# Ethernet.net
KiCad netlist of a schematic drawn in Altium Designer
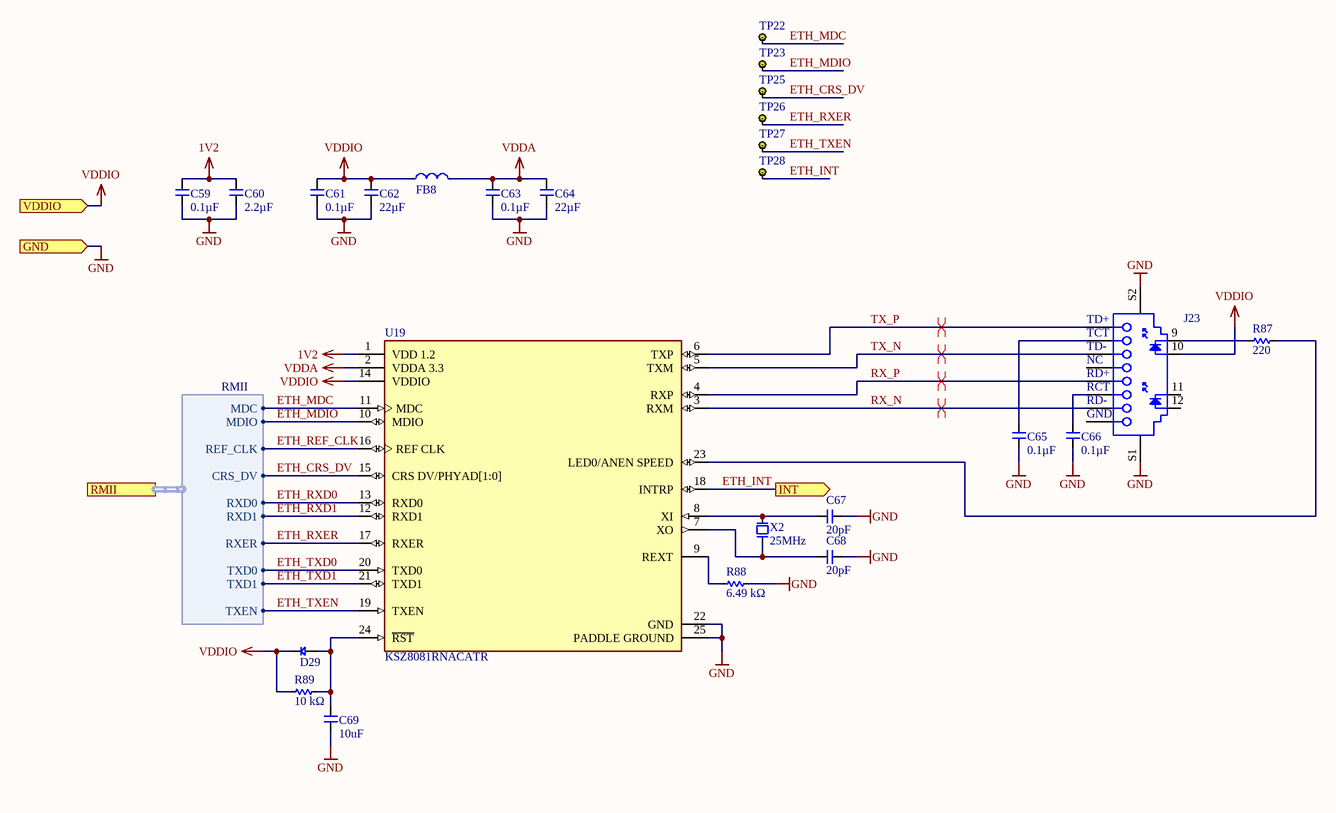
[diagram p0: Ethernet.SchDoc]

(export (version "E")
  (design (tool "Eeschema 10.0.6"))
  (components
    (comp (ref "C59")
      (value "490-1519-1-ND")
      (footprint "C0603")
      (description "CAP CER 0603 0.1µF X7R 50V 10%")
      (fields
        (field (name "MANUFACTURER") "Murata Electronics North America")
        (field (name "CAPACITANCE (SHORTHAND)") "0.1µF")
      )
      (libsource (lib "Stanford Student Space Initiative") (part "__template_cap"))
    )
    (comp (ref "C60")
      (value "490-10731-1-ND")
      (footprint "C0603")
      (description "CAP CER 2.2UF 16V X5R 0603 10%")
      (fields
        (field (name "MANUFACTURER") "Murata Electronics North America")
        (field (name "CAPACITANCE (SHORTHAND)") "2.2µF")
      )
      (libsource (lib "Stanford Student Space Initiative") (part "__template_cap"))
    )
    (comp (ref "C61")
      (value "490-1519-1-ND")
      (footprint "C0603")
      (description "CAP CER 0603 0.1µF X7R 50V 10%")
      (fields
        (field (name "MANUFACTURER") "Murata Electronics North America")
        (field (name "CAPACITANCE (SHORTHAND)") "0.1µF")
      )
      (libsource (lib "Stanford Student Space Initiative") (part "__template_cap"))
    )
    (comp (ref "C62")
      (value "1276-7076-1-ND")
      (footprint "C0603")
      (description "CAP CER 22UF 16V X5R 0603 20%")
      (fields
        (field (name "MANUFACTURER") "Samsung Electro-Mechanics")
        (field (name "CAPACITANCE (SHORTHAND)") "22µF")
      )
      (libsource (lib "Stanford Student Space Initiative") (part "__template_cap"))
    )
    (comp (ref "C63")
      (value "490-1519-1-ND")
      (footprint "C0603")
      (description "CAP CER 0603 0.1µF X7R 50V 10%")
      (fields
        (field (name "MANUFACTURER") "Murata Electronics North America")
        (field (name "CAPACITANCE (SHORTHAND)") "0.1µF")
      )
      (libsource (lib "Stanford Student Space Initiative") (part "__template_cap"))
    )
    (comp (ref "C64")
      (value "1276-7076-1-ND")
      (footprint "C0603")
      (description "CAP CER 22UF 16V X5R 0603 20%")
      (fields
        (field (name "MANUFACTURER") "Samsung Electro-Mechanics")
        (field (name "CAPACITANCE (SHORTHAND)") "22µF")
      )
      (libsource (lib "Stanford Student Space Initiative") (part "__template_cap"))
    )
    (comp (ref "C65")
      (value "490-1519-1-ND")
      (footprint "C0603")
      (description "CAP CER 0603 0.1µF X7R 50V 10%")
      (fields
        (field (name "MANUFACTURER") "Murata Electronics North America")
        (field (name "CAPACITANCE (SHORTHAND)") "0.1µF")
      )
      (libsource (lib "Stanford Student Space Initiative") (part "__template_cap"))
    )
    (comp (ref "C66")
      (value "490-1519-1-ND")
      (footprint "C0603")
      (description "CAP CER 0603 0.1µF X7R 50V 10%")
      (fields
        (field (name "MANUFACTURER") "Murata Electronics North America")
        (field (name "CAPACITANCE (SHORTHAND)") "0.1µF")
      )
      (libsource (lib "Stanford Student Space Initiative") (part "__template_cap"))
    )
    (comp (ref "C67")
      (value "490-1410-1-ND")
      (footprint "C0603")
      (description "CAP CER 20PF 50V C0G/NP0 0603")
      (fields
        (field (name "MANUFACTURER") "Murata Electronics North America")
        (field (name "CAPACITANCE (SHORTHAND)") "20pF")
      )
      (libsource (lib "Stanford Student Space Initiative") (part "__template_cap"))
    )
    (comp (ref "C68")
      (value "490-1410-1-ND")
      (footprint "C0603")
      (description "CAP CER 20PF 50V C0G/NP0 0603")
      (fields
        (field (name "MANUFACTURER") "Murata Electronics North America")
        (field (name "CAPACITANCE (SHORTHAND)") "20pF")
      )
      (libsource (lib "Stanford Student Space Initiative") (part "__template_cap"))
    )
    (comp (ref "C69")
      (value "CAP_CER_10UF_6.3V_20%_X5R_SMD")
      (footprint "C0603")
      (description "CAP CER 10UF 6.3V X5R 0603")
      (fields
        (field (name "CAPACITANCE") "10uF")
        (field (name "MANUFACTURER PART NUMBER") "JMK107BJ106MA-T")
        (field (name "TOLERANCE") "20%")
      )
      (libsource (lib "Stanford Student Space Initiative") (part "CAP_CER_10UF_6.3V_20%_X5R_SMD"))
    )
    (comp (ref "D29")
      (value "DIODE_1N4148WT")
      (footprint "SOD523")
      (description "DIODE SW 75V 4NS SOD-523F")
      (fields
        (field (name "MANUFACTURER") "Fairchild Semiconductor")
        (field (name "MANUFACTURER PART NUMBER") "1N4148WT")
      )
      (libsource (lib "") (part "Symbol_1"))
    )
    (comp (ref "FB8")
      (value "FB_120@100MHz_0603")
      (footprint "C0603")
      (description "FERRITE BEAD 120 OHM @ 100 MHz")
      (fields
        (field (name "MANUFACTURER") "Taiyo Yuden")
        (field (name "MANUFACTURER PART NUMBER") "BKP1608HS121-T")
      )
      (libsource (lib "Stanford Student Space Initiative") (part "FB_120@100MHz_0603"))
    )
    (comp (ref "J23")
      (value "SI-50170-F")
      (footprint "BELS-SI-50170-F_V")
      (description "CONN MAGJACK 1PORT 100 BASE-T")
      (libsource (lib "Stanford Student Space Initiative") (part "RJ45-12-2SHLD"))
    )
    (comp (ref "R87")
      (value "311-220HRCT-ND")
      (footprint "R0603")
      (description "RES SMD 220 OHM 1% 1/10W 0603")
      (fields
        (field (name "MANUFACTURER PART NUMBER") "RC0603FR-07220RL")
        (field (name "MANUFACTURER") "Yageo")
        (field (name "RESISTANCE (SORTABLE)") "220")
      )
      (libsource (lib "Stanford Student Space Initiative") (part "__template_resistor"))
    )
    (comp (ref "R88")
      (value "311-6.49KHRCT-ND")
      (footprint "R0603")
      (description "RES SMD 6.49K OHM 1% 1/10W 0603")
      (fields
        (field (name "TOLERANCE") "±1%")
        (field (name "MANUFACTURER PART NUMBER") "RC0603FR-076K49L")
        (field (name "RESISTANCE") "6.49 kΩ")
      )
      (libsource (lib "Stanford Student Space Initiative") (part "__template_resistor"))
    )
    (comp (ref "R89")
      (value "311-10.0KHRCT-ND")
      (footprint "R0603")
      (description "RES SMD 10K OHM 1% 1/10W 0603")
      (fields
        (field (name "TOLERANCE") "±1%")
        (field (name "MANUFACTURER PART NUMBER") "RC0603FR-0710KL")
        (field (name "RESISTANCE") "10 kΩ")
      )
      (libsource (lib "Stanford Student Space Initiative") (part "__template_resistor"))
    )
    (comp (ref "TP22")
      (value "TEST_POINT_BLACK_KEYSTONE_5001")
      (footprint "TEST_POINT_BLACK_KEYSTONE_5001-Footprint-1")
      (description "BLACK T/H TEST POINT")
      (fields
        (field (name "MANUFACTURER PART NUMBER") "5001")
        (field (name "MANUFACTURER") "Keystone Electronics")
      )
      (libsource (lib "Stanford Student Space Initiative") (part "TEST_POINT_BLACK_KEYSTONE_5001"))
    )
    (comp (ref "TP23")
      (value "TEST_POINT_BLACK_KEYSTONE_5001")
      (footprint "TEST_POINT_BLACK_KEYSTONE_5001-Footprint-1")
      (description "BLACK T/H TEST POINT")
      (fields
        (field (name "MANUFACTURER PART NUMBER") "5001")
        (field (name "MANUFACTURER") "Keystone Electronics")
      )
      (libsource (lib "Stanford Student Space Initiative") (part "TEST_POINT_BLACK_KEYSTONE_5001"))
    )
    (comp (ref "TP25")
      (value "TEST_POINT_BLACK_KEYSTONE_5001")
      (footprint "TEST_POINT_BLACK_KEYSTONE_5001-Footprint-1")
      (description "BLACK T/H TEST POINT")
      (fields
        (field (name "MANUFACTURER PART NUMBER") "5001")
        (field (name "MANUFACTURER") "Keystone Electronics")
      )
      (libsource (lib "Stanford Student Space Initiative") (part "TEST_POINT_BLACK_KEYSTONE_5001"))
    )
    (comp (ref "TP26")
      (value "TEST_POINT_BLACK_KEYSTONE_5001")
      (footprint "TEST_POINT_BLACK_KEYSTONE_5001-Footprint-1")
      (description "BLACK T/H TEST POINT")
      (fields
        (field (name "MANUFACTURER PART NUMBER") "5001")
        (field (name "MANUFACTURER") "Keystone Electronics")
      )
      (libsource (lib "Stanford Student Space Initiative") (part "TEST_POINT_BLACK_KEYSTONE_5001"))
    )
    (comp (ref "TP27")
      (value "TEST_POINT_BLACK_KEYSTONE_5001")
      (footprint "TEST_POINT_BLACK_KEYSTONE_5001-Footprint-1")
      (description "BLACK T/H TEST POINT")
      (fields
        (field (name "MANUFACTURER PART NUMBER") "5001")
        (field (name "MANUFACTURER") "Keystone Electronics")
      )
      (libsource (lib "Stanford Student Space Initiative") (part "TEST_POINT_BLACK_KEYSTONE_5001"))
    )
    (comp (ref "TP28")
      (value "TEST_POINT_BLACK_KEYSTONE_5001")
      (footprint "TEST_POINT_BLACK_KEYSTONE_5001-Footprint-1")
      (description "BLACK T/H TEST POINT")
      (fields
        (field (name "MANUFACTURER PART NUMBER") "5001")
        (field (name "MANUFACTURER") "Keystone Electronics")
      )
      (libsource (lib "Stanford Student Space Initiative") (part "TEST_POINT_BLACK_KEYSTONE_5001"))
    )
    (comp (ref "U19")
      (value "KSZ8081RNACATR")
      (footprint "FP-QFN44-24LD-PL-1-IPC_B")
      (description "Ethernet Controller, 100 Mbps, IEEE 802.3, 3.135 V, 3.465 V, QFN, 24 ;RoHS Compliant: Yes")
      (libsource (lib "Stanford Student Space Initiative") (part "db19a252711fc409187aecce7b8462c"))
    )
    (comp (ref "X2")
      (value "XTAL_ XC1817CT-ND")
      (footprint "4_SMD_3.2X2.5MM")
      (description "25MHz ±10ppm Crystal 20pF 40 Ohm -20°C ~ 70°C Surface Mount 4-SMD, No Lead (DFN, LCC)")
      (fields
        (field (name "FREQUENCY") "25MHz")
        (field (name "MANUFACTURER PART NUMBER") "ECS-250-20-33-CKM-TR")
        (field (name "MANUFACTURER") "ECS Inc.")
      )
      (libsource (lib "Stanford Student Space Initiative") (part "Symbol"))
    )
  )
  (nets
    (net (code "2") (name "/ETH_CRS_DV") (class "Default")
      (node (ref "TP25") (pin "1") (pinfunction "1_1") (pintype "passive"))
      (node (ref "U19") (pin "15") (pinfunction "CRS_DV/PHYAD[1:0]_15") (pintype "bidirectional"))
    )
    (net (code "3") (name "/ETH_INT") (class "Default")
      (node (ref "TP28") (pin "1") (pinfunction "1_1") (pintype "passive"))
      (node (ref "U19") (pin "18") (pinfunction "INTRP_18") (pintype "bidirectional"))
    )
    (net (code "4") (name "/ETH_MDC") (class "Default")
      (node (ref "TP22") (pin "1") (pinfunction "1_1") (pintype "passive"))
      (node (ref "U19") (pin "11") (pinfunction "MDC_11") (pintype "input"))
    )
    (net (code "5") (name "/ETH_MDIO") (class "Default")
      (node (ref "TP23") (pin "1") (pinfunction "1_1") (pintype "passive"))
      (node (ref "U19") (pin "10") (pinfunction "MDIO_10") (pintype "bidirectional"))
    )
    (net (code "6") (name "/ETH_REF_CLK") (class "Default")
      (node (ref "U19") (pin "16") (pinfunction "REF_CLK_16") (pintype "bidirectional"))
    )
    (net (code "7") (name "/ETH_RXD0") (class "Default")
      (node (ref "U19") (pin "13") (pinfunction "RXD0_13") (pintype "bidirectional"))
    )
    (net (code "8") (name "/ETH_RXD1") (class "Default")
      (node (ref "U19") (pin "12") (pinfunction "RXD1_12") (pintype "bidirectional"))
    )
    (net (code "9") (name "/ETH_RXER") (class "Default")
      (node (ref "TP26") (pin "1") (pinfunction "1_1") (pintype "passive"))
      (node (ref "U19") (pin "17") (pinfunction "RXER_17") (pintype "bidirectional"))
    )
    (net (code "10") (name "/ETH_TXD0") (class "Default")
      (node (ref "U19") (pin "20") (pinfunction "TXD0_20") (pintype "input"))
    )
    (net (code "11") (name "/ETH_TXD1") (class "Default")
      (node (ref "U19") (pin "21") (pinfunction "TXD1_21") (pintype "bidirectional"))
    )
    (net (code "12") (name "/ETH_TXEN") (class "Default")
      (node (ref "TP27") (pin "1") (pinfunction "1_1") (pintype "passive"))
      (node (ref "U19") (pin "19") (pinfunction "TXEN_19") (pintype "input"))
    )
    (net (code "13") (name "/RX_N") (class "Default")
      (node (ref "J23") (pin "7") (pinfunction "RD-_7") (pintype "passive"))
      (node (ref "U19") (pin "3") (pinfunction "RXM_3") (pintype "bidirectional"))
    )
    (net (code "14") (name "/RX_P") (class "Default")
      (node (ref "J23") (pin "5") (pinfunction "RD+_5") (pintype "passive"))
      (node (ref "U19") (pin "4") (pinfunction "RXP_4") (pintype "bidirectional"))
    )
    (net (code "15") (name "/TX_N") (class "Default")
      (node (ref "J23") (pin "3") (pinfunction "TD-_3") (pintype "passive"))
      (node (ref "U19") (pin "5") (pinfunction "TXM_5") (pintype "bidirectional"))
    )
    (net (code "16") (name "/TX_P") (class "Default")
      (node (ref "J23") (pin "1") (pinfunction "TD+_1") (pintype "passive"))
      (node (ref "U19") (pin "6") (pinfunction "TXP_6") (pintype "bidirectional"))
    )
    (net (code "18") (name "1V2") (class "Default")
      (node (ref "C59") (pin "1") (pintype "passive"))
      (node (ref "C60") (pin "1") (pintype "passive"))
      (node (ref "U19") (pin "1") (pinfunction "VDD_1.2_1") (pintype "power_in"))
    )
    (net (code "19") (name "GND") (class "Default")
      (node (ref "C59") (pin "2") (pintype "passive"))
      (node (ref "C60") (pin "2") (pintype "passive"))
      (node (ref "C61") (pin "2") (pintype "passive"))
      (node (ref "C62") (pin "2") (pintype "passive"))
      (node (ref "C63") (pin "2") (pintype "passive"))
      (node (ref "C64") (pin "2") (pintype "passive"))
      (node (ref "C65") (pin "2") (pintype "passive"))
      (node (ref "C66") (pin "2") (pintype "passive"))
      (node (ref "C67") (pin "2") (pintype "passive"))
      (node (ref "C68") (pin "2") (pintype "passive"))
      (node (ref "C69") (pin "1") (pintype "passive"))
      (node (ref "J23") (pin "S1") (pinfunction "S1_S1") (pintype "passive"))
      (node (ref "J23") (pin "S2") (pinfunction "S2_S2") (pintype "passive"))
      (node (ref "R88") (pin "1") (pinfunction "1_1") (pintype "passive"))
      (node (ref "U19") (pin "22") (pinfunction "GND_22") (pintype "power_in"))
      (node (ref "U19") (pin "25") (pinfunction "PADDLE_GROUND_25") (pintype "power_in"))
    )
    (net (code "20") (name "Net-(J23-Pad9)") (class "Default")
      (node (ref "J23") (pin "9") (pinfunction "9_9") (pintype "passive"))
      (node (ref "R87") (pin "1") (pinfunction "1_1") (pintype "passive"))
    )
    (net (code "21") (name "Net-(J23-RCT)") (class "Default")
      (node (ref "C66") (pin "1") (pintype "passive"))
      (node (ref "J23") (pin "6") (pinfunction "RCT_6") (pintype "passive"))
    )
    (net (code "22") (name "Net-(J23-TCT)") (class "Default")
      (node (ref "C65") (pin "1") (pintype "passive"))
      (node (ref "J23") (pin "2") (pinfunction "TCT_2") (pintype "passive"))
    )
    (net (code "23") (name "Net-(U19-LED0{slash}ANEN_SPEED)") (class "Default")
      (node (ref "R87") (pin "2") (pinfunction "2_2") (pintype "passive"))
      (node (ref "U19") (pin "23") (pinfunction "LED0/ANEN_SPEED_23") (pintype "bidirectional"))
    )
    (net (code "24") (name "Net-(U19-REXT)") (class "Default")
      (node (ref "R88") (pin "2") (pinfunction "2_2") (pintype "passive"))
      (node (ref "U19") (pin "9") (pinfunction "REXT_9") (pintype "passive"))
    )
    (net (code "25") (name "Net-(U19-XI)") (class "Default")
      (node (ref "C67") (pin "1") (pintype "passive"))
      (node (ref "U19") (pin "8") (pinfunction "XI_8") (pintype "input"))
      (node (ref "X2") (pin "3") (pinfunction "3_3") (pintype "passive"))
    )
    (net (code "26") (name "Net-(U19-XO)") (class "Default")
      (node (ref "C68") (pin "1") (pintype "passive"))
      (node (ref "U19") (pin "7") (pinfunction "XO_7") (pintype "output"))
      (node (ref "X2") (pin "1") (pinfunction "1_1") (pintype "passive"))
    )
    (net (code "27") (name "Net-(U19-~{RST})") (class "Default")
      (node (ref "C69") (pin "2") (pintype "passive"))
      (node (ref "D29") (pin "1") (pintype "passive"))
      (node (ref "R89") (pin "2") (pinfunction "2_2") (pintype "passive"))
      (node (ref "U19") (pin "24") (pinfunction "~{RST}_24") (pintype "input"))
    )
    (net (code "28") (name "VDDA") (class "Default")
      (node (ref "C63") (pin "1") (pintype "passive"))
      (node (ref "C64") (pin "1") (pintype "passive"))
      (node (ref "FB8") (pin "2") (pinfunction "2_2") (pintype "passive"))
      (node (ref "U19") (pin "2") (pinfunction "VDDA_3.3_2") (pintype "power_in"))
    )
    (net (code "29") (name "VDDIO") (class "Default")
      (node (ref "C61") (pin "1") (pintype "passive"))
      (node (ref "C62") (pin "1") (pintype "passive"))
      (node (ref "D29") (pin "2") (pintype "passive"))
      (node (ref "FB8") (pin "1") (pinfunction "1_1") (pintype "passive"))
      (node (ref "J23") (pin "10") (pinfunction "10_10") (pintype "passive"))
      (node (ref "R89") (pin "1") (pinfunction "1_1") (pintype "passive"))
      (node (ref "U19") (pin "14") (pinfunction "VDDIO_14") (pintype "power_in"))
    )
    (net (code "30") (name "unconnected-(J23-GND-Pad8)") (class "Default")
      (node (ref "J23") (pin "8") (pinfunction "GND_8") (pintype "passive"))
    )
    (net (code "31") (name "unconnected-(J23-NC-Pad4)") (class "Default")
      (node (ref "J23") (pin "4") (pinfunction "NC_4") (pintype "passive"))
    )
    (net (code "32") (name "unconnected-(J23-Pad11)") (class "Default")
      (node (ref "J23") (pin "11") (pinfunction "11_11") (pintype "passive"))
    )
    (net (code "33") (name "unconnected-(J23-Pad12)") (class "Default")
      (node (ref "J23") (pin "12") (pinfunction "12_12") (pintype "passive"))
    )
  )
)
